# ProPrj___2024-09-03.net
KiCad netlist of a schematic drawn in EasyEDA Pro
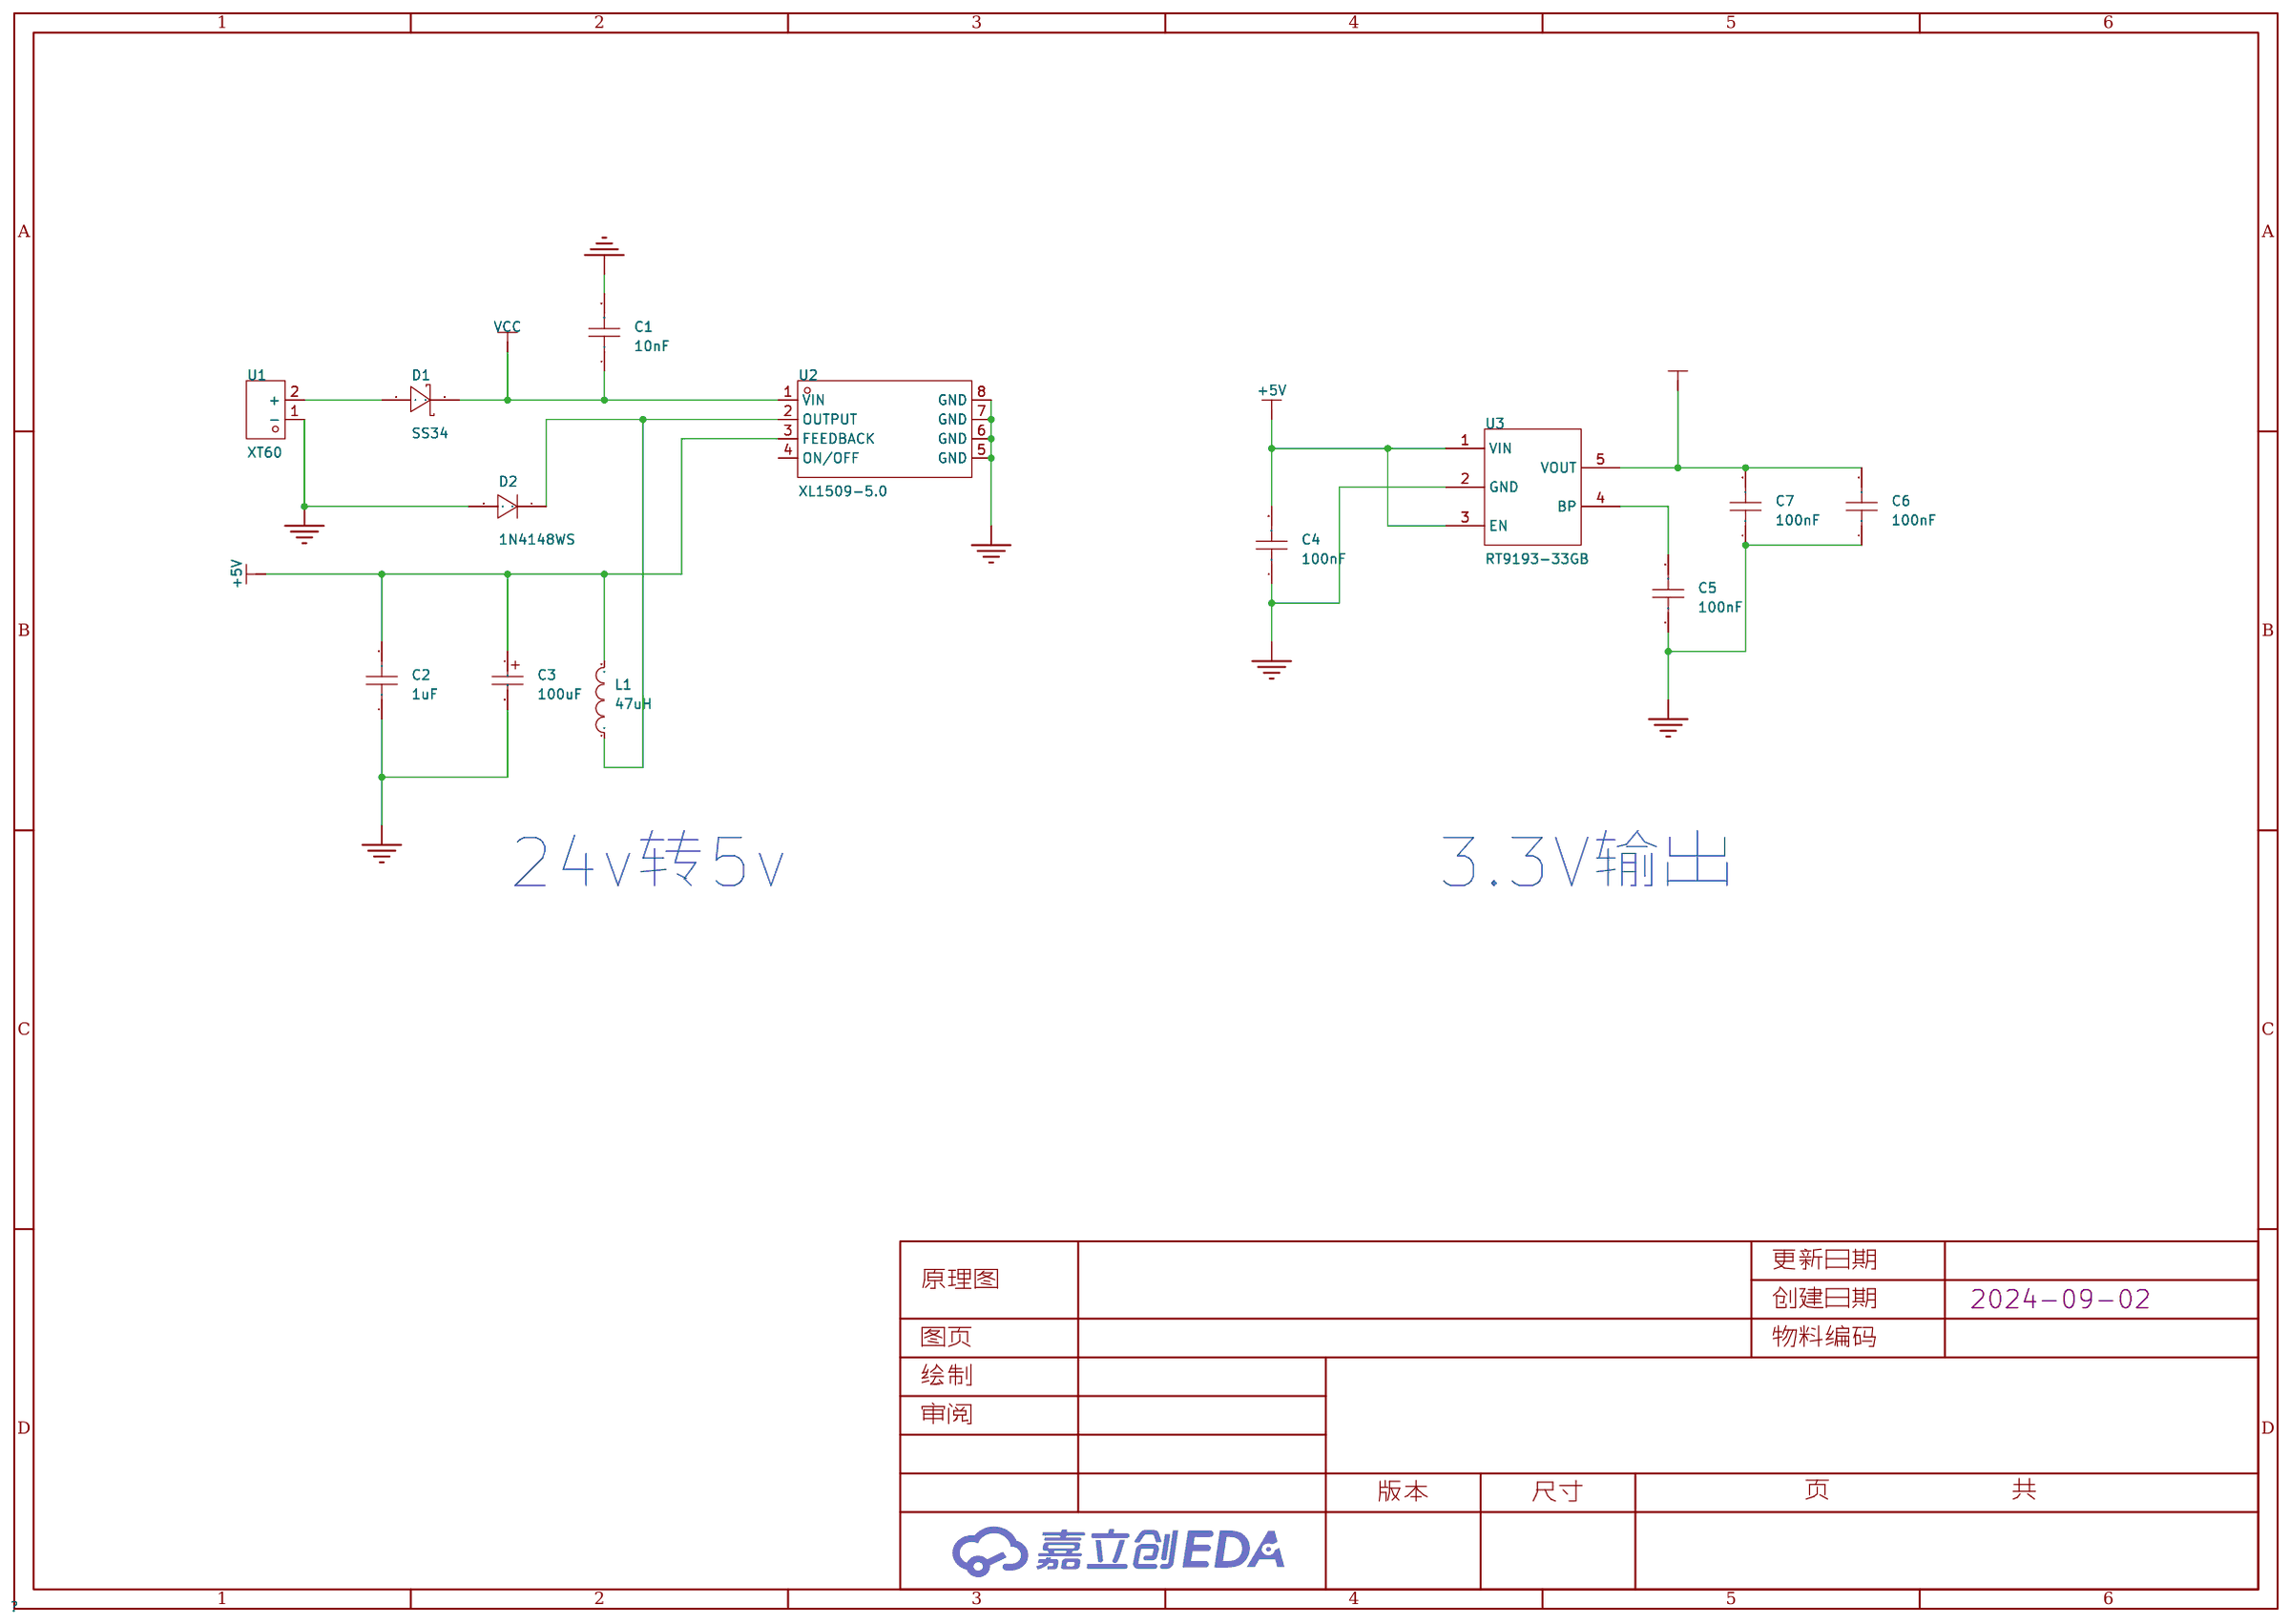
[diagram p0: schematic sheet]

(export (version "E")
  (design (tool "Eeschema 10.0.6"))
  (components
    (comp (ref "C1")
      (value "10nF")
      (footprint "easyedapro:C0603")
      (libsource (lib "easyedapro") (part "CapAcitance"))
    )
    (comp (ref "C2")
      (value "1uF")
      (footprint "easyedapro:C0603")
      (libsource (lib "easyedapro") (part "CapAcitance"))
    )
    (comp (ref "C3")
      (value "100uF")
      (footprint "easyedapro:C_Ele_SMD_3x5.4mm")
      (libsource (lib "easyedapro") (part "CAP"))
    )
    (comp (ref "C4")
      (value "100nF")
      (footprint "easyedapro:C0603")
      (libsource (lib "easyedapro") (part "CapAcitance"))
    )
    (comp (ref "C5")
      (value "100nF")
      (footprint "easyedapro:C0603")
      (libsource (lib "easyedapro") (part "CapAcitance"))
    )
    (comp (ref "C6")
      (value "100nF")
      (footprint "easyedapro:C0603")
      (libsource (lib "easyedapro") (part "CapAcitance"))
    )
    (comp (ref "C7")
      (value "100nF")
      (footprint "easyedapro:C0603")
      (libsource (lib "easyedapro") (part "CapAcitance"))
    )
    (comp (ref "D1")
      (value "SS34")
      (footprint "easyedapro:SMA_L4.3-W2.6-LS5.2-RD")
      (description "二极管配置:独立式;正向压降(Vf):550mV@3A;直流反向耐压(Vr):40V;整流电流:3A;")
      (fields (field (name "Manufacturer") "MDD(辰达半导体)"))
      (libsource (lib "easyedapro") (part "SS34_C8678"))
    )
    (comp (ref "D2")
      (value "1N4148WS")
      (footprint "easyedapro:SOD-323_L1.8-W1.3-LS2.5-RD")
      (description "二极管配置:独立式;正向压降(Vf):1.25V@150mA;直流反向耐压(Vr):100V;平均整流电流(Io):150mA;功率:200mW;反向恢复时间(trr):4ns;")
      (fields (field (name "Manufacturer") "CJ(江苏长电/长晶)"))
      (libsource (lib "easyedapro") (part "1N4148WS T4"))
    )
    (comp (ref "L1")
      (value "47uH")
      (footprint "easyedapro:L0603")
      (libsource (lib "easyedapro") (part "SDFL1608S100KTF"))
    )
    (comp (ref "U1")
      (value "XT60")
      (footprint "easyedapro:CONN-TH_XT60")
      (description "类别:-;类型1:-;")
      (fields (field (name "Manufacturer") "AMASS(艾迈斯)"))
      (libsource (lib "easyedapro") (part "XT60"))
    )
    (comp (ref "U2")
      (value "XL1509-5.0")
      (footprint "easyedapro:SOIC-8_L4.9-W3.9-P1.27-LS6.0-TR")
      (fields (field (name "Manufacturer") "UMW(友台半导体)"))
      (libsource (lib "easyedapro") (part "XL1509-5.0_C2902368"))
    )
    (comp (ref "U3")
      (value "RT9193-33GB")
      (footprint "easyedapro:SOT-23-5_L3.0-W1.7-P0.95-LS2.8-BL")
      (description "输出类型:固定;最大输入电压:5.5V;输出电压:3.3V;最大输出电流:300mA;电源纹波抑制比(PSRR):70dB;输出极性:正极;")
      (fields (field (name "Manufacturer") "RICHTEK(立锜)"))
      (libsource (lib "easyedapro") (part "RT9193-33GB"))
    )
  )
  (nets
    (net (code "1") (name "+5V") (class "Default")
      (node (ref "C2") (pin "2") (pinfunction "2_2") (pintype "input"))
      (node (ref "C3") (pin "1") (pinfunction "1_1") (pintype "input"))
      (node (ref "C4") (pin "2") (pinfunction "2_2") (pintype "input"))
      (node (ref "L1") (pin "2") (pinfunction "2_2") (pintype "unspecified"))
      (node (ref "U2") (pin "3") (pinfunction "FEEDBACK_3") (pintype "unspecified"))
      (node (ref "U3") (pin "1") (pinfunction "VIN_1") (pintype "unspecified"))
      (node (ref "U3") (pin "3") (pinfunction "EN_3") (pintype "unspecified"))
    )
    (net (code "2") (name "3.3V") (class "Default")
      (node (ref "C6") (pin "2") (pinfunction "2_2") (pintype "input"))
      (node (ref "C7") (pin "2") (pinfunction "2_2") (pintype "input"))
      (node (ref "U3") (pin "5") (pinfunction "VOUT_5") (pintype "unspecified"))
    )
    (net (code "3") (name "GND") (class "Default")
      (node (ref "C1") (pin "2") (pinfunction "2_2") (pintype "input"))
      (node (ref "C2") (pin "1") (pinfunction "1_1") (pintype "input"))
      (node (ref "C3") (pin "2") (pinfunction "2_2") (pintype "input"))
      (node (ref "C4") (pin "1") (pinfunction "1_1") (pintype "input"))
      (node (ref "C5") (pin "1") (pinfunction "1_1") (pintype "input"))
      (node (ref "C6") (pin "1") (pinfunction "1_1") (pintype "input"))
      (node (ref "C7") (pin "1") (pinfunction "1_1") (pintype "input"))
      (node (ref "D2") (pin "2") (pinfunction "A_2") (pintype "unspecified"))
      (node (ref "U1") (pin "1") (pinfunction "-_1") (pintype "input"))
      (node (ref "U2") (pin "5") (pinfunction "GND_5") (pintype "unspecified"))
      (node (ref "U2") (pin "6") (pinfunction "GND_6") (pintype "unspecified"))
      (node (ref "U2") (pin "7") (pinfunction "GND_7") (pintype "unspecified"))
      (node (ref "U2") (pin "8") (pinfunction "GND_8") (pintype "unspecified"))
      (node (ref "U3") (pin "2") (pinfunction "GND_2") (pintype "unspecified"))
    )
    (net (code "4") (name "Net-(D1-A)") (class "Default")
      (node (ref "D1") (pin "2") (pinfunction "A_2") (pintype "unspecified"))
      (node (ref "U1") (pin "2") (pinfunction "+_2") (pintype "input"))
    )
    (net (code "5") (name "Net-(D2-K)") (class "Default")
      (node (ref "D2") (pin "1") (pinfunction "K_1") (pintype "unspecified"))
      (node (ref "L1") (pin "1") (pinfunction "1_1") (pintype "unspecified"))
      (node (ref "U2") (pin "2") (pinfunction "OUTPUT_2") (pintype "unspecified"))
    )
    (net (code "6") (name "Net-(U3-BP)") (class "Default")
      (node (ref "C5") (pin "2") (pinfunction "2_2") (pintype "input"))
      (node (ref "U3") (pin "4") (pinfunction "BP_4") (pintype "unspecified"))
    )
    (net (code "7") (name "VCC") (class "Default")
      (node (ref "C1") (pin "1") (pinfunction "1_1") (pintype "input"))
      (node (ref "D1") (pin "1") (pinfunction "K_1") (pintype "unspecified"))
      (node (ref "U2") (pin "1") (pinfunction "VIN_1") (pintype "unspecified"))
    )
    (net (code "8") (name "unconnected-(U2-ON{slash}OFF-Pad4)") (class "Default")
      (node (ref "U2") (pin "4") (pinfunction "ON/OFF_4") (pintype "unspecified"))
    )
  )
)
